# DiAoPu.net
KiCad netlist of a schematic drawn in Altium Designer
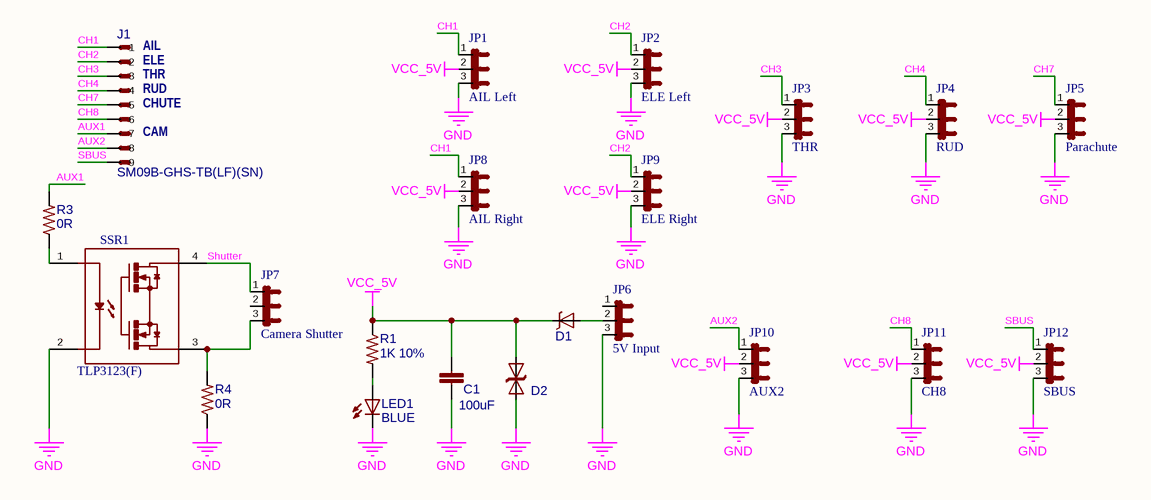
[diagram p0: DiAoPu.SchDoc]

(export (version "E")
  (design (tool "Eeschema 10.0.6"))
  (components
    (comp (ref "C1")
      (value "100uF")
      (footprint "1210-CAP")
      (description "<b>Capacitor</b>\nStandard 0603 ceramic capacitor, and 0.1\" leaded capacitor.")
      (fields (field (name "PARTNO") "GRM32ER71H475K"))
      (libsource (lib "pixhawk2") (part "CAP0402-CAP"))
    )
    (comp (ref "D1")
      (value "Schottky barrier diode in DO214AC, e.g. Fairchild SS14.")
      (footprint "DO-214AA")
      (libsource (lib "pixhawk2") (part "DIODE-SCHOTTKY_SMA"))
    )
    (comp (ref "D2")
      (value "DIODE-Bi−Directional TVS")
      (footprint "DO-214AA")
      (libsource (lib "pixhawk2") (part "DIODE-Bi−Directional TVS"))
    )
    (comp (ref "J1")
      (value "SM09B-GHS-TB(LF)(SN)")
      (footprint "SM09B-GHS-TB(LF)")
      (libsource (lib "pixhawk2") (part "SM09B-GHS-TB(LF)(SN)"))
    )
    (comp (ref "JP1")
      (value "AIL Left")
      (footprint "SJ_3 2MM Pitch")
      (libsource (lib "pixhawk2") (part "JUMPER-3SMD"))
    )
    (comp (ref "JP2")
      (value "ELE Left")
      (footprint "SJ_3 2MM Pitch")
      (libsource (lib "pixhawk2") (part "JUMPER-3SMD"))
    )
    (comp (ref "JP3")
      (value "THR")
      (footprint "SJ_3 2MM Pitch")
      (libsource (lib "pixhawk2") (part "JUMPER-3SMD"))
    )
    (comp (ref "JP4")
      (value "RUD")
      (footprint "SJ_3 2MM Pitch")
      (libsource (lib "pixhawk2") (part "JUMPER-3SMD"))
    )
    (comp (ref "JP5")
      (value "Parachute")
      (footprint "SJ_3 2MM Pitch")
      (libsource (lib "pixhawk2") (part "JUMPER-3SMD"))
    )
    (comp (ref "JP6")
      (value "5V Input")
      (footprint "SJ_3 2MM Pitch")
      (libsource (lib "pixhawk2") (part "JUMPER-3SMD"))
    )
    (comp (ref "JP7")
      (value "Camera Shutter")
      (footprint "SJ_3 2MM Pitch")
      (libsource (lib "pixhawk2") (part "JUMPER-3SMD"))
    )
    (comp (ref "JP8")
      (value "AIL Right")
      (footprint "SJ_3 2MM Pitch")
      (libsource (lib "pixhawk2") (part "JUMPER-3SMD"))
    )
    (comp (ref "JP9")
      (value "ELE Right")
      (footprint "SJ_3 2MM Pitch")
      (libsource (lib "pixhawk2") (part "JUMPER-3SMD"))
    )
    (comp (ref "JP10")
      (value "AUX2")
      (footprint "SJ_3 2MM Pitch")
      (libsource (lib "pixhawk2") (part "JUMPER-3SMD"))
    )
    (comp (ref "JP11")
      (value "CH8")
      (footprint "SJ_3 2MM Pitch")
      (libsource (lib "pixhawk2") (part "JUMPER-3SMD"))
    )
    (comp (ref "JP12")
      (value "SBUS")
      (footprint "SJ_3 2MM Pitch")
      (libsource (lib "pixhawk2") (part "JUMPER-3SMD"))
    )
    (comp (ref "LED1") (value "BLUE") (footprint "0603-LED") (libsource (lib "pixhawk2") (part "LED0603")))
    (comp (ref "R1")
      (value "1K 10%")
      (footprint "0603-RES")
      (libsource (lib "pixhawk2") (part "RESISTOR0603-RES"))
    )
    (comp (ref "R3")
      (value "0R")
      (footprint "0603-RES")
      (libsource (lib "pixhawk2") (part "RESISTOR0603-RES"))
    )
    (comp (ref "R4")
      (value "0R")
      (footprint "0603-RES")
      (libsource (lib "pixhawk2") (part "RESISTOR0603-RES"))
    )
    (comp (ref "SSR1")
      (value "TLP3123(F)")
      (footprint "SOP4-2.54")
      (libsource (lib "pixhawk2") (part "TLP3123SO"))
    )
  )
  (nets
    (net (code "1") (name "/AUX1") (class "Default")
      (node (ref "J1") (pin "7") (pinfunction "7_7") (pintype "passive"))
      (node (ref "R3") (pin "2") (pinfunction "2_2") (pintype "passive"))
    )
    (net (code "2") (name "/AUX2") (class "Default")
      (node (ref "J1") (pin "8") (pinfunction "8_8") (pintype "passive"))
      (node (ref "JP10") (pin "1") (pinfunction "1_1") (pintype "passive"))
    )
    (net (code "3") (name "/CH1") (class "Default")
      (node (ref "J1") (pin "1") (pinfunction "1_1") (pintype "passive"))
      (node (ref "JP1") (pin "1") (pinfunction "1_1") (pintype "passive"))
      (node (ref "JP8") (pin "1") (pinfunction "1_1") (pintype "passive"))
    )
    (net (code "4") (name "/CH2") (class "Default")
      (node (ref "J1") (pin "2") (pinfunction "2_2") (pintype "passive"))
      (node (ref "JP2") (pin "1") (pinfunction "1_1") (pintype "passive"))
      (node (ref "JP9") (pin "1") (pinfunction "1_1") (pintype "passive"))
    )
    (net (code "5") (name "/CH3") (class "Default")
      (node (ref "J1") (pin "3") (pinfunction "3_3") (pintype "passive"))
      (node (ref "JP3") (pin "1") (pinfunction "1_1") (pintype "passive"))
    )
    (net (code "6") (name "/CH4") (class "Default")
      (node (ref "J1") (pin "4") (pinfunction "4_4") (pintype "passive"))
      (node (ref "JP4") (pin "1") (pinfunction "1_1") (pintype "passive"))
    )
    (net (code "7") (name "/CH7") (class "Default")
      (node (ref "J1") (pin "5") (pinfunction "5_5") (pintype "passive"))
      (node (ref "JP5") (pin "1") (pinfunction "1_1") (pintype "passive"))
    )
    (net (code "8") (name "/CH8") (class "Default")
      (node (ref "J1") (pin "6") (pinfunction "6_6") (pintype "passive"))
      (node (ref "JP11") (pin "1") (pinfunction "1_1") (pintype "passive"))
    )
    (net (code "9") (name "/SBUS") (class "Default")
      (node (ref "J1") (pin "9") (pinfunction "9_9") (pintype "passive"))
      (node (ref "JP12") (pin "1") (pinfunction "1_1") (pintype "passive"))
    )
    (net (code "10") (name "/Shutter") (class "Default")
      (node (ref "JP7") (pin "1") (pinfunction "1_1") (pintype "passive"))
      (node (ref "SSR1") (pin "4") (pinfunction "4_4") (pintype "passive"))
    )
    (net (code "11") (name "GND") (class "Default")
      (node (ref "C1") (pin "2") (pinfunction "2_2") (pintype "passive"))
      (node (ref "D2") (pin "A") (pinfunction "A_A") (pintype "passive"))
      (node (ref "JP1") (pin "3") (pinfunction "3_3") (pintype "passive"))
      (node (ref "JP10") (pin "3") (pinfunction "3_3") (pintype "passive"))
      (node (ref "JP11") (pin "3") (pinfunction "3_3") (pintype "passive"))
      (node (ref "JP12") (pin "3") (pinfunction "3_3") (pintype "passive"))
      (node (ref "JP2") (pin "3") (pinfunction "3_3") (pintype "passive"))
      (node (ref "JP3") (pin "3") (pinfunction "3_3") (pintype "passive"))
      (node (ref "JP4") (pin "3") (pinfunction "3_3") (pintype "passive"))
      (node (ref "JP5") (pin "3") (pinfunction "3_3") (pintype "passive"))
      (node (ref "JP6") (pin "3") (pinfunction "3_3") (pintype "passive"))
      (node (ref "JP8") (pin "3") (pinfunction "3_3") (pintype "passive"))
      (node (ref "JP9") (pin "3") (pinfunction "3_3") (pintype "passive"))
      (node (ref "LED1") (pin "C") (pinfunction "C_C") (pintype "passive"))
      (node (ref "R4") (pin "1") (pinfunction "1_1") (pintype "passive"))
      (node (ref "SSR1") (pin "2") (pinfunction "2_2") (pintype "passive"))
    )
    (net (code "12") (name "Net-(D1-PadA)") (class "Default")
      (node (ref "D1") (pin "A") (pinfunction "A_A") (pintype "passive"))
      (node (ref "JP6") (pin "2") (pinfunction "2_2") (pintype "passive"))
    )
    (net (code "13") (name "Net-(JP7-Pad3)") (class "Default")
      (node (ref "JP7") (pin "3") (pinfunction "3_3") (pintype "passive"))
      (node (ref "R4") (pin "2") (pinfunction "2_2") (pintype "passive"))
      (node (ref "SSR1") (pin "3") (pinfunction "3_3") (pintype "passive"))
    )
    (net (code "14") (name "Net-(LED1-PadA)") (class "Default")
      (node (ref "LED1") (pin "A") (pinfunction "A_A") (pintype "passive"))
      (node (ref "R1") (pin "2") (pinfunction "2_2") (pintype "passive"))
    )
    (net (code "15") (name "Net-(R3-Pad1)") (class "Default")
      (node (ref "R3") (pin "1") (pinfunction "1_1") (pintype "passive"))
      (node (ref "SSR1") (pin "1") (pinfunction "1_1") (pintype "passive"))
    )
    (net (code "16") (name "VCC_5V") (class "Default")
      (node (ref "C1") (pin "1") (pinfunction "1_1") (pintype "passive"))
      (node (ref "D1") (pin "C") (pinfunction "C_C") (pintype "passive"))
      (node (ref "D2") (pin "C") (pinfunction "C_C") (pintype "passive"))
      (node (ref "JP1") (pin "2") (pinfunction "2_2") (pintype "passive"))
      (node (ref "JP10") (pin "2") (pinfunction "2_2") (pintype "passive"))
      (node (ref "JP11") (pin "2") (pinfunction "2_2") (pintype "passive"))
      (node (ref "JP12") (pin "2") (pinfunction "2_2") (pintype "passive"))
      (node (ref "JP2") (pin "2") (pinfunction "2_2") (pintype "passive"))
      (node (ref "JP3") (pin "2") (pinfunction "2_2") (pintype "passive"))
      (node (ref "JP4") (pin "2") (pinfunction "2_2") (pintype "passive"))
      (node (ref "JP5") (pin "2") (pinfunction "2_2") (pintype "passive"))
      (node (ref "JP8") (pin "2") (pinfunction "2_2") (pintype "passive"))
      (node (ref "JP9") (pin "2") (pinfunction "2_2") (pintype "passive"))
      (node (ref "R1") (pin "1") (pinfunction "1_1") (pintype "passive"))
    )
    (net (code "17") (name "unconnected-(JP6-Pad1)") (class "Default")
      (node (ref "JP6") (pin "1") (pinfunction "1_1") (pintype "passive"))
    )
    (net (code "18") (name "unconnected-(JP7-Pad2)") (class "Default")
      (node (ref "JP7") (pin "2") (pinfunction "2_2") (pintype "passive"))
    )
  )
)
